# MCU.net
KiCad netlist of a schematic drawn in Altium Designer
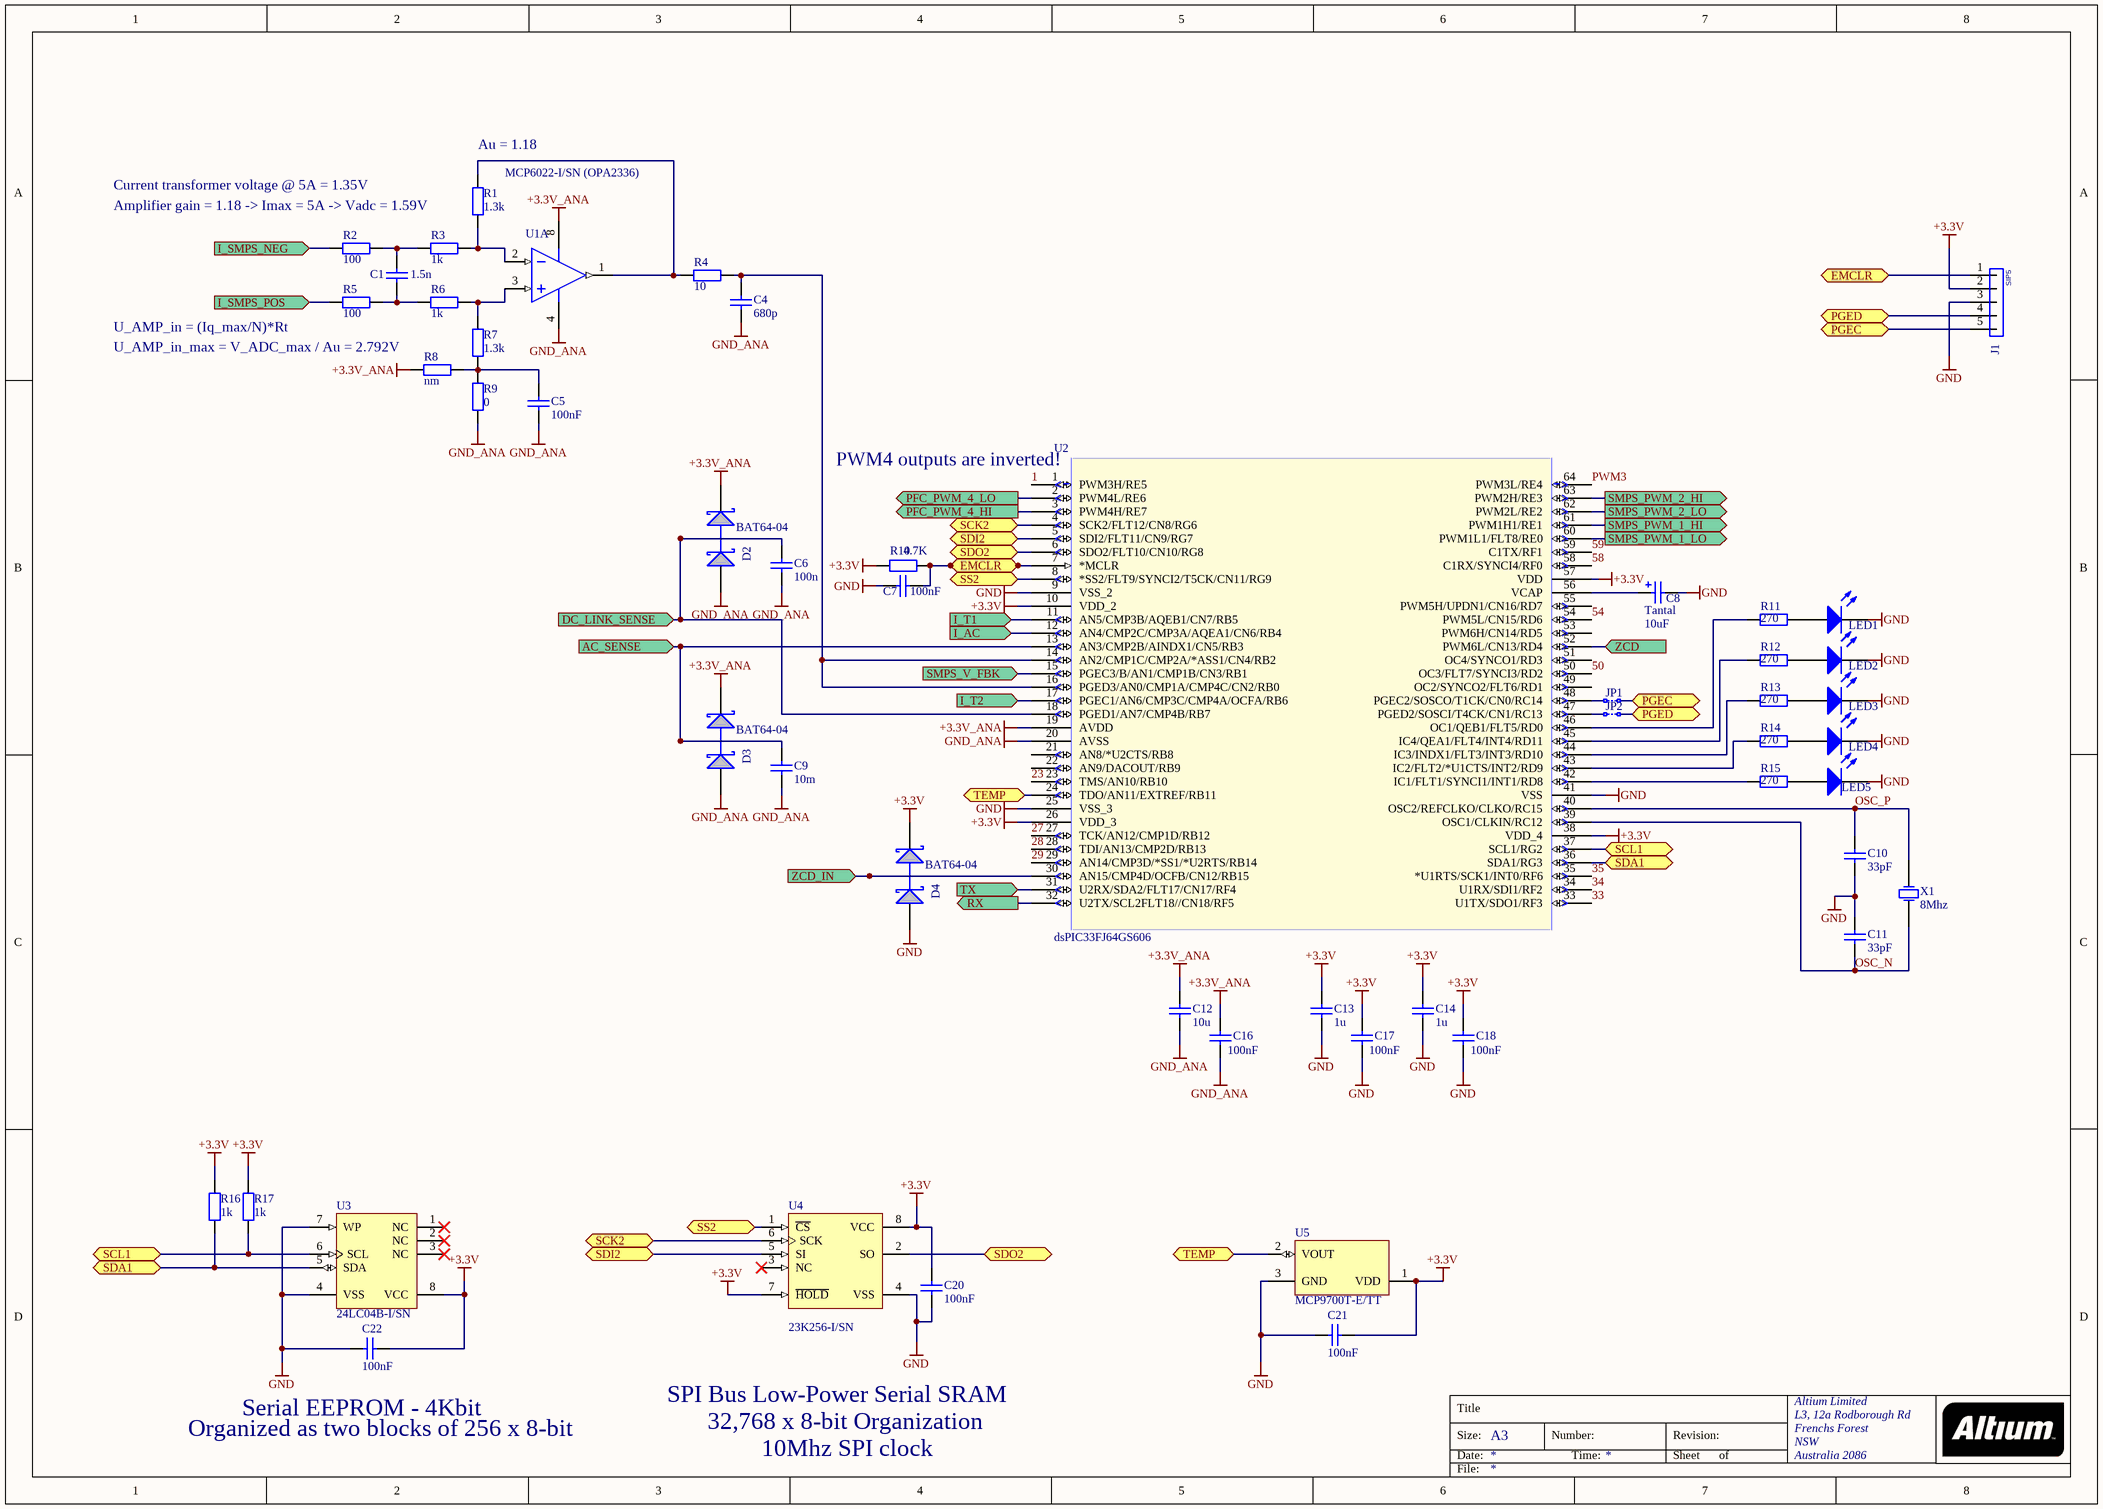
[diagram p0: MCU.SchDoc]

(export (version "E")
  (design (tool "Eeschema 10.0.6"))
  (components
    (comp (ref "C1")
      (value "1.5n")
      (footprint "1206_REFLOW")
      (fields (field (name "Comment") "Cap"))
      (libsource (lib "Capacitors") (part "Cap"))
    )
    (comp (ref "C4")
      (value "680p")
      (footprint "1206_REFLOW")
      (fields (field (name "Comment") "Cap"))
      (libsource (lib "Capacitors") (part "Cap"))
    )
    (comp (ref "C5")
      (value "100nF")
      (footprint "1206_REFLOW")
      (fields (field (name "Comment") "Cap"))
      (libsource (lib "Capacitors") (part "Cap"))
    )
    (comp (ref "C6")
      (value "100n")
      (footprint "1206_REFLOW")
      (fields (field (name "Comment") "Cap 1206"))
      (libsource (lib "Capacitors") (part "Cap 1206"))
    )
    (comp (ref "C7")
      (value "100nF")
      (footprint "1206_REFLOW")
      (fields (field (name "Comment") "Cap 1206"))
      (libsource (lib "Capacitors") (part "Cap 1206"))
    )
    (comp (ref "C8")
      (value "Tantal")
      (footprint "CASE D")
      (fields (field (name "ALTIUM_VALUE") "10uF"))
      (libsource (lib "Capacitors") (part "CAP CASE D"))
    )
    (comp (ref "C9")
      (value "10m")
      (footprint "1206_REFLOW")
      (fields (field (name "Comment") "Cap 1206"))
      (libsource (lib "Capacitors") (part "Cap 1206"))
    )
    (comp (ref "C10")
      (value "33pF")
      (footprint "1206_REFLOW")
      (fields (field (name "Comment") "Cap"))
      (libsource (lib "Capacitors") (part "Cap"))
    )
    (comp (ref "C11")
      (value "33pF")
      (footprint "1206_REFLOW")
      (fields (field (name "Comment") "Cap"))
      (libsource (lib "Capacitors") (part "Cap"))
    )
    (comp (ref "C12")
      (value "10u")
      (footprint "1206_REFLOW")
      (fields (field (name "Comment") "Cap 1206"))
      (libsource (lib "Capacitors") (part "Cap 1206"))
    )
    (comp (ref "C13")
      (value "1u")
      (footprint "1206_REFLOW")
      (fields (field (name "Comment") "Cap 1206"))
      (libsource (lib "Capacitors") (part "Cap 1206"))
    )
    (comp (ref "C14")
      (value "1u")
      (footprint "1206_REFLOW")
      (fields (field (name "Comment") "Cap 1206"))
      (libsource (lib "Capacitors") (part "Cap 1206"))
    )
    (comp (ref "C16")
      (value "100nF")
      (footprint "1206_REFLOW")
      (fields (field (name "Comment") "Cap 1206"))
      (libsource (lib "Capacitors") (part "Cap 1206"))
    )
    (comp (ref "C17")
      (value "100nF")
      (footprint "1206_REFLOW")
      (fields (field (name "Comment") "Cap 1206"))
      (libsource (lib "Capacitors") (part "Cap 1206"))
    )
    (comp (ref "C18")
      (value "100nF")
      (footprint "1206_REFLOW")
      (fields (field (name "Comment") "Cap 1206"))
      (libsource (lib "Capacitors") (part "Cap 1206"))
    )
    (comp (ref "C20")
      (value "100nF")
      (footprint "1206_REFLOW")
      (fields (field (name "Comment") "Cap 1206"))
      (libsource (lib "Capacitors") (part "Cap 1206"))
    )
    (comp (ref "C21")
      (value "100nF")
      (footprint "1206_REFLOW")
      (fields (field (name "Comment") "Cap 1206"))
      (libsource (lib "Capacitors") (part "Cap 1206"))
    )
    (comp (ref "C22")
      (value "100nF")
      (footprint "1206_REFLOW")
      (fields (field (name "Comment") "Cap 1206"))
      (libsource (lib "Capacitors") (part "Cap 1206"))
    )
    (comp (ref "D2")
      (value "BAT64-04")
      (footprint "SOT23_HIS_Primary")
      (description "Silicon Schottky Diodes")
      (fields (field (name "MANUFACTURER") "INF") (field (name "PUBLISHER") "Altium Limited"))
      (libsource (lib "Diode") (part "BAT64-04"))
    )
    (comp (ref "D3")
      (value "BAT64-04")
      (footprint "SOT23_HIS_Primary")
      (description "Silicon Schottky Diodes")
      (fields (field (name "MANUFACTURER") "INF") (field (name "PUBLISHER") "Altium Limited"))
      (libsource (lib "Diode") (part "BAT64-04"))
    )
    (comp (ref "D4")
      (value "BAT64-04")
      (footprint "SOT23_HIS_Primary")
      (description "Silicon Schottky Diodes")
      (fields (field (name "MANUFACTURER") "INF") (field (name "PUBLISHER") "Altium Limited"))
      (libsource (lib "Diode") (part "BAT64-04"))
    )
    (comp (ref "J1") (value "SIP5") (footprint "SIP5 _2") (libsource (lib "Connector") (part "SIP5")))
    (comp (ref "JP1")
      (value "SOLDERCONTACT")
      (footprint "SOLDERCONTACT")
      (libsource (lib "Connector") (part "SOLDERCONTACT"))
    )
    (comp (ref "JP2")
      (value "SOLDERCONTACT")
      (footprint "SOLDERCONTACT")
      (libsource (lib "Connector") (part "SOLDERCONTACT"))
    )
    (comp (ref "LED1") (value "LED") (footprint "LED_1206") (libsource (lib "LED") (part "LED")))
    (comp (ref "LED2") (value "LED") (footprint "LED_1206") (libsource (lib "LED") (part "LED")))
    (comp (ref "LED3") (value "LED") (footprint "LED_1206") (libsource (lib "LED") (part "LED")))
    (comp (ref "LED4") (value "LED") (footprint "LED_1206") (libsource (lib "LED") (part "LED")))
    (comp (ref "LED5") (value "LED") (footprint "LED_1206") (libsource (lib "LED") (part "LED")))
    (comp (ref "R1")
      (value "1.3k")
      (footprint "1206_REFLOW")
      (fields (field (name "Comment") "RES"))
      (libsource (lib "") (part "RES 1_1"))
    )
    (comp (ref "R2")
      (value "100")
      (footprint "1206_REFLOW")
      (fields (field (name "TOLERANCE") "1%") (field (name "Comment") "RES"))
      (libsource (lib "Resistor") (part "RES 1"))
    )
    (comp (ref "R3")
      (value "1k")
      (footprint "1206_REFLOW")
      (fields (field (name "TOLERANCE") "1%") (field (name "Comment") "RES"))
      (libsource (lib "Resistor") (part "RES 1"))
    )
    (comp (ref "R4")
      (value "10")
      (footprint "1206_REFLOW")
      (fields (field (name "TOLERANCE") "1%") (field (name "Comment") "RES"))
      (libsource (lib "") (part "RES 1_3"))
    )
    (comp (ref "R5")
      (value "100")
      (footprint "1206_REFLOW")
      (fields (field (name "TOLERANCE") "1%") (field (name "Comment") "RES"))
      (libsource (lib "Resistor") (part "RES 1"))
    )
    (comp (ref "R6")
      (value "1k")
      (footprint "1206_REFLOW")
      (fields (field (name "TOLERANCE") "1%") (field (name "Comment") "RES"))
      (libsource (lib "Resistor") (part "RES 1"))
    )
    (comp (ref "R7")
      (value "1.3k")
      (footprint "1206_REFLOW")
      (fields (field (name "Comment") "RES"))
      (libsource (lib "") (part "RES 1_1"))
    )
    (comp (ref "R8")
      (value "nm")
      (footprint "1206_REFLOW")
      (fields (field (name "Comment") "RES"))
      (libsource (lib "Resistor") (part "RES 1"))
    )
    (comp (ref "R9")
      (value "0")
      (footprint "1206_REFLOW")
      (fields (field (name "Comment") "RES"))
      (libsource (lib "") (part "RES 1_1"))
    )
    (comp (ref "R10")
      (value "4.7K")
      (footprint "1206_REFLOW")
      (fields (field (name "Comment") "RES"))
      (libsource (lib "Resistor") (part "RES 1"))
    )
    (comp (ref "R11")
      (value "270")
      (footprint "1206_REFLOW")
      (fields (field (name "Comment") "RES"))
      (libsource (lib "Resistor") (part "RES 1"))
    )
    (comp (ref "R12")
      (value "270")
      (footprint "1206_REFLOW")
      (fields (field (name "Comment") "RES"))
      (libsource (lib "Resistor") (part "RES 1"))
    )
    (comp (ref "R13")
      (value "270")
      (footprint "1206_REFLOW")
      (fields (field (name "Comment") "RES"))
      (libsource (lib "Resistor") (part "RES 1"))
    )
    (comp (ref "R14")
      (value "270")
      (footprint "1206_REFLOW")
      (fields (field (name "Comment") "RES"))
      (libsource (lib "Resistor") (part "RES 1"))
    )
    (comp (ref "R15")
      (value "270")
      (footprint "1206_REFLOW")
      (fields (field (name "Comment") "RES"))
      (libsource (lib "Resistor") (part "RES 1"))
    )
    (comp (ref "R16")
      (value "1k")
      (footprint "1206_REFLOW")
      (fields (field (name "Comment") "RES"))
      (libsource (lib "") (part "RES 1_2"))
    )
    (comp (ref "R17")
      (value "1k")
      (footprint "1206_REFLOW")
      (fields (field (name "Comment") "RES"))
      (libsource (lib "") (part "RES 1_2"))
    )
    (comp (ref "U1")
      (value "MCP6022-I/SN (OPA2336)")
      (footprint "SOIC-SN8_N")
      (description "Rail-to-Rail Input/Output, 10 MHz Operational Amplifier, 8-Pin SOIC, Industrial Temperature")
      (fields (field (name "PUBLISHER") "Altium Limited"))
      (libsource (lib "Microchip Linear Devices") (part "MCP6022-I/SN"))
    )
    (comp (ref "U2")
      (value "dsPIC33FJ64GS606")
      (footprint "TQFP-PT64_N")
      (libsource (lib "Microchip MCU") (part "dsPIC33FJ64GS606"))
    )
    (comp (ref "U3")
      (value "24LC04B-I/SN")
      (footprint "SOIC-SN8_N")
      (description "4Kbit, 400kHz, 2.5V, I2C Serial EEPROM, 8-Pin SOIC 150mil, Industrial Temperature")
      (fields (field (name "PUBLISHER") "Altium Limited"))
      (libsource (lib "Microchip EEPROM I2C Serial") (part "24LC04B-I/SN"))
    )
    (comp (ref "U4")
      (value "23K256-I/SN")
      (footprint "SOIC-SN8_N")
      (description "IC, SRAM, SERIAL, 256K, 2.7V, SOIC8")
      (libsource (lib "Microchip EEPROM SPI Serial") (part "25LC640AT-I/SN"))
    )
    (comp (ref "U5")
      (value "MCP9700T-E/TT")
      (footprint "SOT-23-TT3_N")
      (description "Low-Power Linear Active Thermistor IC, 3-Pin SOT-23, Extended Temperature, Tape and Reel")
      (fields (field (name "PUBLISHER") "Altium Limited"))
      (libsource (lib "Microchip Thermal Management") (part "MCP9700T-E/TT"))
    )
    (comp (ref "X1")
      (value "8Mhz")
      (footprint "XTAL")
      (fields (field (name "Comment") "XTAL"))
      (libsource (lib "Oscillator") (part "XTAL"))
    )
  )
  (nets
    (net (code "1") (name "+3.3V") (class "Default")
      (node (ref "C13") (pin "2") (pinfunction "2_2") (pintype "passive"))
      (node (ref "C14") (pin "2") (pinfunction "2_2") (pintype "passive"))
      (node (ref "C17") (pin "2") (pinfunction "2_2") (pintype "passive"))
      (node (ref "C18") (pin "2") (pinfunction "2_2") (pintype "passive"))
      (node (ref "C20") (pin "1") (pinfunction "1_1") (pintype "passive"))
      (node (ref "C21") (pin "1") (pinfunction "1_1") (pintype "passive"))
      (node (ref "C22") (pin "1") (pinfunction "1_1") (pintype "passive"))
      (node (ref "D4") (pin "2") (pinfunction "K_2") (pintype "passive"))
      (node (ref "J1") (pin "2") (pintype "passive"))
      (node (ref "R10") (pin "1") (pinfunction "1_1") (pintype "passive"))
      (node (ref "R16") (pin "1") (pinfunction "1_1") (pintype "passive"))
      (node (ref "R17") (pin "1") (pinfunction "1_1") (pintype "passive"))
      (node (ref "U2") (pin "10") (pinfunction "VDD_2_10") (pintype "power_in"))
      (node (ref "U2") (pin "26") (pinfunction "VDD_3_26") (pintype "power_in"))
      (node (ref "U2") (pin "38") (pinfunction "VDD_4_38") (pintype "power_in"))
      (node (ref "U2") (pin "57") (pinfunction "VDD_57") (pintype "power_in"))
      (node (ref "U3") (pin "8") (pinfunction "VCC_8") (pintype "power_in"))
      (node (ref "U4") (pin "7") (pinfunction "~{HOLD}_7") (pintype "input"))
      (node (ref "U4") (pin "8") (pinfunction "VCC_8") (pintype "power_in"))
      (node (ref "U5") (pin "1") (pinfunction "VDD_1") (pintype "power_in"))
    )
    (net (code "2") (name "+3.3V_ANA") (class "Default")
      (node (ref "C12") (pin "2") (pinfunction "2_2") (pintype "passive"))
      (node (ref "C16") (pin "2") (pinfunction "2_2") (pintype "passive"))
      (node (ref "D2") (pin "2") (pinfunction "K_2") (pintype "passive"))
      (node (ref "D3") (pin "2") (pinfunction "K_2") (pintype "passive"))
      (node (ref "R8") (pin "1") (pinfunction "1_1") (pintype "passive"))
      (node (ref "U1") (pin "8") (pinfunction "VDD_8") (pintype "power_in"))
      (node (ref "U2") (pin "19") (pinfunction "AVDD_19") (pintype "power_in"))
    )
    (net (code "3") (name "/1") (class "Default")
      (node (ref "U2") (pin "1") (pinfunction "PWM3H/RE5_1") (pintype "bidirectional"))
    )
    (net (code "4") (name "/23") (class "Default")
      (node (ref "U2") (pin "23") (pinfunction "TMS/AN10/RB10_23") (pintype "bidirectional"))
    )
    (net (code "5") (name "/27") (class "Default")
      (node (ref "U2") (pin "27") (pinfunction "TCK/AN12/CMP1D/RB12_27") (pintype "bidirectional"))
    )
    (net (code "6") (name "/28") (class "Default")
      (node (ref "U2") (pin "28") (pinfunction "TDI/AN13/CMP2D/RB13_28") (pintype "bidirectional"))
    )
    (net (code "7") (name "/29") (class "Default")
      (node (ref "U2") (pin "29") (pinfunction "AN14/CMP3D/*SS1/*U2RTS/RB14_29") (pintype "bidirectional"))
    )
    (net (code "8") (name "/33") (class "Default")
      (node (ref "U2") (pin "33") (pinfunction "U1TX/SDO1/RF3_33") (pintype "bidirectional"))
    )
    (net (code "9") (name "/34") (class "Default")
      (node (ref "U2") (pin "34") (pinfunction "U1RX/SDI1/RF2_34") (pintype "bidirectional"))
    )
    (net (code "10") (name "/35") (class "Default")
      (node (ref "U2") (pin "35") (pinfunction "*U1RTS/SCK1/INT0/RF6_35") (pintype "bidirectional"))
    )
    (net (code "11") (name "/50") (class "Default")
      (node (ref "U2") (pin "50") (pinfunction "OC3/FLT7/SYNCI3/RD2_50") (pintype "bidirectional"))
    )
    (net (code "12") (name "/54") (class "Default")
      (node (ref "U2") (pin "54") (pinfunction "PWM5L/CN15/RD6_54") (pintype "bidirectional"))
    )
    (net (code "13") (name "/58") (class "Default")
      (node (ref "U2") (pin "58") (pinfunction "C1RX/SYNCI4/RF0_58") (pintype "bidirectional"))
    )
    (net (code "14") (name "/59") (class "Default")
      (node (ref "U2") (pin "59") (pinfunction "C1TX/RF1_59") (pintype "bidirectional"))
    )
    (net (code "15") (name "/AC_SENSE") (class "Default")
      (node (ref "C9") (pin "2") (pinfunction "2_2") (pintype "passive"))
      (node (ref "D3") (pin "3") (pinfunction "C_3") (pintype "passive"))
      (node (ref "U2") (pin "13") (pinfunction "AN3/CMP2B/AINDX1/CN5/RB3_13") (pintype "bidirectional"))
    )
    (net (code "16") (name "/DC_LINK_SENSE") (class "Default")
      (node (ref "C6") (pin "2") (pinfunction "2_2") (pintype "passive"))
      (node (ref "D2") (pin "3") (pinfunction "C_3") (pintype "passive"))
      (node (ref "U2") (pin "18") (pinfunction "PGED1/AN7/CMP4B/RB7_18") (pintype "bidirectional"))
    )
    (net (code "17") (name "/EMCLR") (class "Default")
      (node (ref "C7") (pin "2") (pinfunction "2_2") (pintype "passive"))
      (node (ref "J1") (pin "1") (pintype "passive"))
      (node (ref "R10") (pin "2") (pinfunction "2_2") (pintype "passive"))
      (node (ref "U2") (pin "7") (pinfunction "*MCLR_7") (pintype "input"))
    )
    (net (code "18") (name "/I_AC") (class "Default")
      (node (ref "U2") (pin "12") (pinfunction "AN4/CMP2C/CMP3A/AQEA1/CN6/RB4_12") (pintype "bidirectional"))
    )
    (net (code "19") (name "/I_SMPS_NEG") (class "Default")
      (node (ref "R2") (pin "1") (pinfunction "1_1") (pintype "passive"))
    )
    (net (code "20") (name "/I_SMPS_POS") (class "Default")
      (node (ref "R5") (pin "1") (pinfunction "1_1") (pintype "passive"))
    )
    (net (code "21") (name "/I_T1") (class "Default")
      (node (ref "U2") (pin "11") (pinfunction "AN5/CMP3B/AQEB1/CN7/RB5_11") (pintype "bidirectional"))
    )
    (net (code "22") (name "/I_T2") (class "Default")
      (node (ref "U2") (pin "17") (pinfunction "PGEC1/AN6/CMP3C/CMP4A/OCFA/RB6_17") (pintype "bidirectional"))
    )
    (net (code "23") (name "/OSC_N") (class "Default")
      (node (ref "C11") (pin "1") (pinfunction "1_1") (pintype "passive"))
      (node (ref "U2") (pin "39") (pinfunction "OSC1/CLKIN/RC12_39") (pintype "bidirectional"))
      (node (ref "X1") (pin "1") (pinfunction "OSC1_1") (pintype "passive"))
    )
    (net (code "24") (name "/OSC_P") (class "Default")
      (node (ref "C10") (pin "2") (pinfunction "2_2") (pintype "passive"))
      (node (ref "U2") (pin "40") (pinfunction "OSC2/REFCLKO/CLKO/RC15_40") (pintype "bidirectional"))
      (node (ref "X1") (pin "2") (pinfunction "OSC2_2") (pintype "passive"))
    )
    (net (code "25") (name "/PFC_PWM_4_HI") (class "Default")
      (node (ref "U2") (pin "3") (pinfunction "PWM4H/RE7_3") (pintype "bidirectional"))
    )
    (net (code "26") (name "/PFC_PWM_4_LO") (class "Default")
      (node (ref "U2") (pin "2") (pinfunction "PWM4L/RE6_2") (pintype "bidirectional"))
    )
    (net (code "27") (name "/PGEC") (class "Default")
      (node (ref "J1") (pin "5") (pintype "passive"))
      (node (ref "JP1") (pin "2") (pinfunction "2_2") (pintype "passive"))
    )
    (net (code "28") (name "/PGED") (class "Default")
      (node (ref "J1") (pin "4") (pintype "passive"))
      (node (ref "JP2") (pin "1") (pinfunction "1_1") (pintype "passive"))
    )
    (net (code "29") (name "/PWM3") (class "Default")
      (node (ref "U2") (pin "64") (pinfunction "PWM3L/RE4_64") (pintype "bidirectional"))
    )
    (net (code "30") (name "/RX") (class "Default")
      (node (ref "U2") (pin "32") (pinfunction "U2TX/SCL2FLT18//CN18/RF5_32") (pintype "bidirectional"))
    )
    (net (code "31") (name "/SCK2") (class "Default")
      (node (ref "U2") (pin "4") (pinfunction "SCK2/FLT12/CN8/RG6_4") (pintype "bidirectional"))
      (node (ref "U4") (pin "6") (pinfunction "SCK_6") (pintype "input"))
    )
    (net (code "32") (name "/SCL1") (class "Default")
      (node (ref "R17") (pin "2") (pinfunction "2_2") (pintype "passive"))
      (node (ref "U2") (pin "37") (pinfunction "SCL1/RG2_37") (pintype "bidirectional"))
      (node (ref "U3") (pin "6") (pinfunction "SCL_6") (pintype "input"))
    )
    (net (code "33") (name "/SDA1") (class "Default")
      (node (ref "R16") (pin "2") (pinfunction "2_2") (pintype "passive"))
      (node (ref "U2") (pin "36") (pinfunction "SDA1/RG3_36") (pintype "bidirectional"))
      (node (ref "U3") (pin "5") (pinfunction "SDA_5") (pintype "bidirectional"))
    )
    (net (code "34") (name "/SDI2") (class "Default")
      (node (ref "U2") (pin "5") (pinfunction "SDI2/FLT11/CN9/RG7_5") (pintype "bidirectional"))
      (node (ref "U4") (pin "5") (pinfunction "SI_5") (pintype "input"))
    )
    (net (code "35") (name "/SDO2") (class "Default")
      (node (ref "U2") (pin "6") (pinfunction "SDO2/FLT10/CN10/RG8_6") (pintype "bidirectional"))
      (node (ref "U4") (pin "2") (pinfunction "SO_2") (pintype "tri_state"))
    )
    (net (code "36") (name "/SMPS_PWM_1_HI") (class "Default")
      (node (ref "U2") (pin "61") (pinfunction "PWM1H1/RE1_61") (pintype "bidirectional"))
    )
    (net (code "37") (name "/SMPS_PWM_1_LO") (class "Default")
      (node (ref "U2") (pin "60") (pinfunction "PWM1L1/FLT8/RE0_60") (pintype "bidirectional"))
    )
    (net (code "38") (name "/SMPS_PWM_2_HI") (class "Default")
      (node (ref "U2") (pin "63") (pinfunction "PWM2H/RE3_63") (pintype "bidirectional"))
    )
    (net (code "39") (name "/SMPS_PWM_2_LO") (class "Default")
      (node (ref "U2") (pin "62") (pinfunction "PWM2L/RE2_62") (pintype "bidirectional"))
    )
    (net (code "40") (name "/SMPS_V_FBK") (class "Default")
      (node (ref "U2") (pin "15") (pinfunction "PGEC3/B/AN1/CMP1B/CN3/RB1_15") (pintype "bidirectional"))
    )
    (net (code "41") (name "/SS2") (class "Default")
      (node (ref "U2") (pin "8") (pinfunction "*SS2/FLT9/SYNCI2/T5CK/CN11/RG9_8") (pintype "bidirectional"))
      (node (ref "U4") (pin "1") (pinfunction "~{CS}_1") (pintype "input"))
    )
    (net (code "42") (name "/TEMP") (class "Default")
      (node (ref "U2") (pin "24") (pinfunction "TDO/AN11/EXTREF/RB11_24") (pintype "bidirectional"))
      (node (ref "U5") (pin "2") (pinfunction "VOUT_2") (pintype "bidirectional"))
    )
    (net (code "43") (name "/TX") (class "Default")
      (node (ref "U2") (pin "31") (pinfunction "U2RX/SDA2/FLT17/CN17/RF4_31") (pintype "bidirectional"))
    )
    (net (code "44") (name "/ZCD") (class "Default")
      (node (ref "U2") (pin "52") (pinfunction "PWM6L/CN13/RD4_52") (pintype "bidirectional"))
    )
    (net (code "45") (name "/ZCD_IN") (class "Default")
      (node (ref "D4") (pin "3") (pinfunction "C_3") (pintype "passive"))
      (node (ref "U2") (pin "30") (pinfunction "AN15/CMP4D/OCFB/CN12/RB15_30") (pintype "bidirectional"))
    )
    (net (code "46") (name "GND") (class "Default")
      (node (ref "C10") (pin "1") (pinfunction "1_1") (pintype "passive"))
      (node (ref "C11") (pin "2") (pinfunction "2_2") (pintype "passive"))
      (node (ref "C13") (pin "1") (pinfunction "1_1") (pintype "passive"))
      (node (ref "C14") (pin "1") (pinfunction "1_1") (pintype "passive"))
      (node (ref "C17") (pin "1") (pinfunction "1_1") (pintype "passive"))
      (node (ref "C18") (pin "1") (pinfunction "1_1") (pintype "passive"))
      (node (ref "C20") (pin "2") (pinfunction "2_2") (pintype "passive"))
      (node (ref "C21") (pin "2") (pinfunction "2_2") (pintype "passive"))
      (node (ref "C22") (pin "2") (pinfunction "2_2") (pintype "passive"))
      (node (ref "C7") (pin "1") (pinfunction "1_1") (pintype "passive"))
      (node (ref "C8") (pin "2") (pinfunction "2_2") (pintype "passive"))
      (node (ref "D4") (pin "1") (pinfunction "A_1") (pintype "passive"))
      (node (ref "J1") (pin "3") (pintype "passive"))
      (node (ref "LED1") (pin "K") (pinfunction "K_K") (pintype "passive"))
      (node (ref "LED2") (pin "K") (pinfunction "K_K") (pintype "passive"))
      (node (ref "LED3") (pin "K") (pinfunction "K_K") (pintype "passive"))
      (node (ref "LED4") (pin "K") (pinfunction "K_K") (pintype "passive"))
      (node (ref "LED5") (pin "K") (pinfunction "K_K") (pintype "passive"))
      (node (ref "U2") (pin "25") (pinfunction "VSS_3_25") (pintype "power_in"))
      (node (ref "U2") (pin "41") (pinfunction "VSS_41") (pintype "power_in"))
      (node (ref "U2") (pin "9") (pinfunction "VSS_2_9") (pintype "power_in"))
      (node (ref "U3") (pin "4") (pinfunction "VSS_4") (pintype "power_in"))
      (node (ref "U3") (pin "7") (pinfunction "WP_7") (pintype "input"))
      (node (ref "U4") (pin "4") (pinfunction "VSS_4") (pintype "power_in"))
      (node (ref "U5") (pin "3") (pinfunction "GND_3") (pintype "power_in"))
    )
    (net (code "47") (name "GND_ANA") (class "Default")
      (node (ref "C12") (pin "1") (pinfunction "1_1") (pintype "passive"))
      (node (ref "C16") (pin "1") (pinfunction "1_1") (pintype "passive"))
      (node (ref "C4") (pin "1") (pinfunction "1_1") (pintype "passive"))
      (node (ref "C5") (pin "1") (pinfunction "1_1") (pintype "passive"))
      (node (ref "C6") (pin "1") (pinfunction "1_1") (pintype "passive"))
      (node (ref "C9") (pin "1") (pinfunction "1_1") (pintype "passive"))
      (node (ref "D2") (pin "1") (pinfunction "A_1") (pintype "passive"))
      (node (ref "D3") (pin "1") (pinfunction "A_1") (pintype "passive"))
      (node (ref "R9") (pin "1") (pinfunction "1_1") (pintype "passive"))
      (node (ref "U1") (pin "4") (pinfunction "VSS_4") (pintype "power_in"))
      (node (ref "U2") (pin "20") (pinfunction "AVSS_20") (pintype "power_in"))
    )
    (net (code "48") (name "Net-(C1-Pad1)") (class "Default")
      (node (ref "C1") (pin "1") (pinfunction "1_1") (pintype "passive"))
      (node (ref "R5") (pin "2") (pinfunction "2_2") (pintype "passive"))
      (node (ref "R6") (pin "1") (pinfunction "1_1") (pintype "passive"))
    )
    (net (code "49") (name "Net-(C1-Pad2)") (class "Default")
      (node (ref "C1") (pin "2") (pinfunction "2_2") (pintype "passive"))
      (node (ref "R2") (pin "2") (pinfunction "2_2") (pintype "passive"))
      (node (ref "R3") (pin "1") (pinfunction "1_1") (pintype "passive"))
    )
    (net (code "50") (name "Net-(C5-Pad2)") (class "Default")
      (node (ref "C5") (pin "2") (pinfunction "2_2") (pintype "passive"))
      (node (ref "R7") (pin "1") (pinfunction "1_1") (pintype "passive"))
      (node (ref "R8") (pin "2") (pinfunction "2_2") (pintype "passive"))
      (node (ref "R9") (pin "2") (pinfunction "2_2") (pintype "passive"))
    )
    (net (code "51") (name "Net-(LED1-PadA)") (class "Default")
      (node (ref "LED1") (pin "A") (pinfunction "A_A") (pintype "passive"))
      (node (ref "R11") (pin "2") (pinfunction "2_2") (pintype "passive"))
    )
    (net (code "52") (name "Net-(LED2-PadA)") (class "Default")
      (node (ref "LED2") (pin "A") (pinfunction "A_A") (pintype "passive"))
      (node (ref "R12") (pin "2") (pinfunction "2_2") (pintype "passive"))
    )
    (net (code "53") (name "Net-(LED3-PadA)") (class "Default")
      (node (ref "LED3") (pin "A") (pinfunction "A_A") (pintype "passive"))
      (node (ref "R13") (pin "2") (pinfunction "2_2") (pintype "passive"))
    )
    (net (code "54") (name "Net-(LED4-PadA)") (class "Default")
      (node (ref "LED4") (pin "A") (pinfunction "A_A") (pintype "passive"))
      (node (ref "R14") (pin "2") (pinfunction "2_2") (pintype "passive"))
    )
    (net (code "55") (name "Net-(LED5-PadA)") (class "Default")
      (node (ref "LED5") (pin "A") (pinfunction "A_A") (pintype "passive"))
      (node (ref "R15") (pin "2") (pinfunction "2_2") (pintype "passive"))
    )
    (net (code "56") (name "Net-(U1A-VINA+)") (class "Default")
      (node (ref "R6") (pin "2") (pinfunction "2_2") (pintype "passive"))
      (node (ref "R7") (pin "2") (pinfunction "2_2") (pintype "passive"))
      (node (ref "U1") (pin "3") (pinfunction "VINA+_3") (pintype "input"))
    )
    (net (code "57") (name "Net-(U1A-VINA-)") (class "Default")
      (node (ref "R1") (pin "1") (pinfunction "1_1") (pintype "passive"))
      (node (ref "R3") (pin "2") (pinfunction "2_2") (pintype "passive"))
      (node (ref "U1") (pin "2") (pinfunction "VINA-_2") (pintype "input"))
    )
    (net (code "58") (name "Net-(U1A-VOUTA)") (class "Default")
      (node (ref "R1") (pin "2") (pinfunction "2_2") (pintype "passive"))
      (node (ref "R4") (pin "2") (pinfunction "2_2") (pintype "passive"))
      (node (ref "U1") (pin "1") (pinfunction "VOUTA_1") (pintype "output"))
    )
    (net (code "59") (name "Net-(U2-AN2{slash}CMP1C{slash}CMP2A{slash}*ASS1{slash}CN4{slash}RB2)") (class "Default")
      (node (ref "C4") (pin "2") (pinfunction "2_2") (pintype "passive"))
      (node (ref "R4") (pin "1") (pinfunction "1_1") (pintype "passive"))
      (node (ref "U2") (pin "14") (pinfunction "AN2/CMP1C/CMP2A/*ASS1/CN4/RB2_14") (pintype "bidirectional"))
      (node (ref "U2") (pin "16") (pinfunction "PGED3/AN0/CMP1A/CMP4C/CN2/RB0_16") (pintype "bidirectional"))
    )
    (net (code "60") (name "Net-(U2-IC1{slash}FLT1{slash}SYNCI1{slash}INT1{slash}RD8)") (class "Default")
      (node (ref "R15") (pin "1") (pinfunction "1_1") (pintype "passive"))
      (node (ref "U2") (pin "42") (pinfunction "IC1/FLT1/SYNCI1/INT1/RD8_42") (pintype "bidirectional"))
    )
    (net (code "61") (name "Net-(U2-IC2{slash}FLT2{slash}*U1CTS{slash}INT2{slash}RD9)") (class "Default")
      (node (ref "R14") (pin "1") (pinfunction "1_1") (pintype "passive"))
      (node (ref "U2") (pin "43") (pinfunction "IC2/FLT2/*U1CTS/INT2/RD9_43") (pintype "bidirectional"))
    )
    (net (code "62") (name "Net-(U2-IC3{slash}INDX1{slash}FLT3{slash}INT3{slash}RD10)") (class "Default")
      (node (ref "R13") (pin "1") (pinfunction "1_1") (pintype "passive"))
      (node (ref "U2") (pin "44") (pinfunction "IC3/INDX1/FLT3/INT3/RD10_44") (pintype "bidirectional"))
    )
    (net (code "63") (name "Net-(U2-IC4{slash}QEA1{slash}FLT4{slash}INT4{slash}RD11)") (class "Default")
      (node (ref "R12") (pin "1") (pinfunction "1_1") (pintype "passive"))
      (node (ref "U2") (pin "45") (pinfunction "IC4/QEA1/FLT4/INT4/RD11_45") (pintype "bidirectional"))
    )
    (net (code "64") (name "Net-(U2-OC1{slash}QEB1{slash}FLT5{slash}RD0)") (class "Default")
      (node (ref "R11") (pin "1") (pinfunction "1_1") (pintype "passive"))
      (node (ref "U2") (pin "46") (pinfunction "OC1/QEB1/FLT5/RD0_46") (pintype "bidirectional"))
    )
    (net (code "65") (name "Net-(U2-PGEC2{slash}SOSCO{slash}T1CK{slash}CN0{slash}RC14)") (class "Default")
      (node (ref "JP1") (pin "1") (pinfunction "1_1") (pintype "passive"))
      (node (ref "U2") (pin "48") (pinfunction "PGEC2/SOSCO/T1CK/CN0/RC14_48") (pintype "bidirectional"))
    )
    (net (code "66") (name "Net-(U2-PGED2{slash}SOSCI{slash}T4CK{slash}CN1{slash}RC13)") (class "Default")
      (node (ref "JP2") (pin "2") (pinfunction "2_2") (pintype "passive"))
      (node (ref "U2") (pin "47") (pinfunction "PGED2/SOSCI/T4CK/CN1/RC13_47") (pintype "bidirectional"))
    )
    (net (code "67") (name "Net-(U2-VCAP)") (class "Default")
      (node (ref "C8") (pin "1") (pinfunction "1_1") (pintype "passive"))
      (node (ref "U2") (pin "56") (pinfunction "VCAP_56") (pintype "power_in"))
    )
    (net (code "68") (name "unconnected-(U2-AN8{slash}*U2CTS{slash}RB8-Pad21)") (class "Default")
      (node (ref "U2") (pin "21") (pinfunction "AN8/*U2CTS/RB8_21") (pintype "bidirectional"))
    )
    (net (code "69") (name "unconnected-(U2-AN9{slash}DACOUT{slash}RB9-Pad22)") (class "Default")
      (node (ref "U2") (pin "22") (pinfunction "AN9/DACOUT/RB9_22") (pintype "bidirectional"))
    )
    (net (code "70") (name "unconnected-(U2-OC2{slash}SYNCO2{slash}FLT6{slash}RD1-Pad49)") (class "Default")
      (node (ref "U2") (pin "49") (pinfunction "OC2/SYNCO2/FLT6/RD1_49") (pintype "bidirectional"))
    )
    (net (code "71") (name "unconnected-(U2-OC4{slash}SYNCO1{slash}RD3-Pad51)") (class "Default")
      (node (ref "U2") (pin "51") (pinfunction "OC4/SYNCO1/RD3_51") (pintype "bidirectional"))
    )
    (net (code "72") (name "unconnected-(U2-PWM5H{slash}UPDN1{slash}CN16{slash}RD7-Pad55)") (class "Default")
      (node (ref "U2") (pin "55") (pinfunction "PWM5H/UPDN1/CN16/RD7_55") (pintype "bidirectional"))
    )
    (net (code "73") (name "unconnected-(U2-PWM6H{slash}CN14{slash}RD5-Pad53)") (class "Default")
      (node (ref "U2") (pin "53") (pinfunction "PWM6H/CN14/RD5_53") (pintype "bidirectional"))
    )
    (net (code "74") (name "unconnected-(U3-NC-Pad1)") (class "Default")
      (node (ref "U3") (pin "1") (pinfunction "NC_1") (pintype "passive+no_connect"))
    )
    (net (code "75") (name "unconnected-(U3-NC-Pad2)") (class "Default")
      (node (ref "U3") (pin "2") (pinfunction "NC_2") (pintype "passive+no_connect"))
    )
    (net (code "76") (name "unconnected-(U3-NC-Pad3)") (class "Default")
      (node (ref "U3") (pin "3") (pinfunction "NC_3") (pintype "passive+no_connect"))
    )
    (net (code "77") (name "unconnected-(U4-NC-Pad3)") (class "Default")
      (node (ref "U4") (pin "3") (pinfunction "NC_3") (pintype "input+no_connect"))
    )
  )
)
